# RWatch.net
KiCad netlist of a schematic drawn in EAGLE
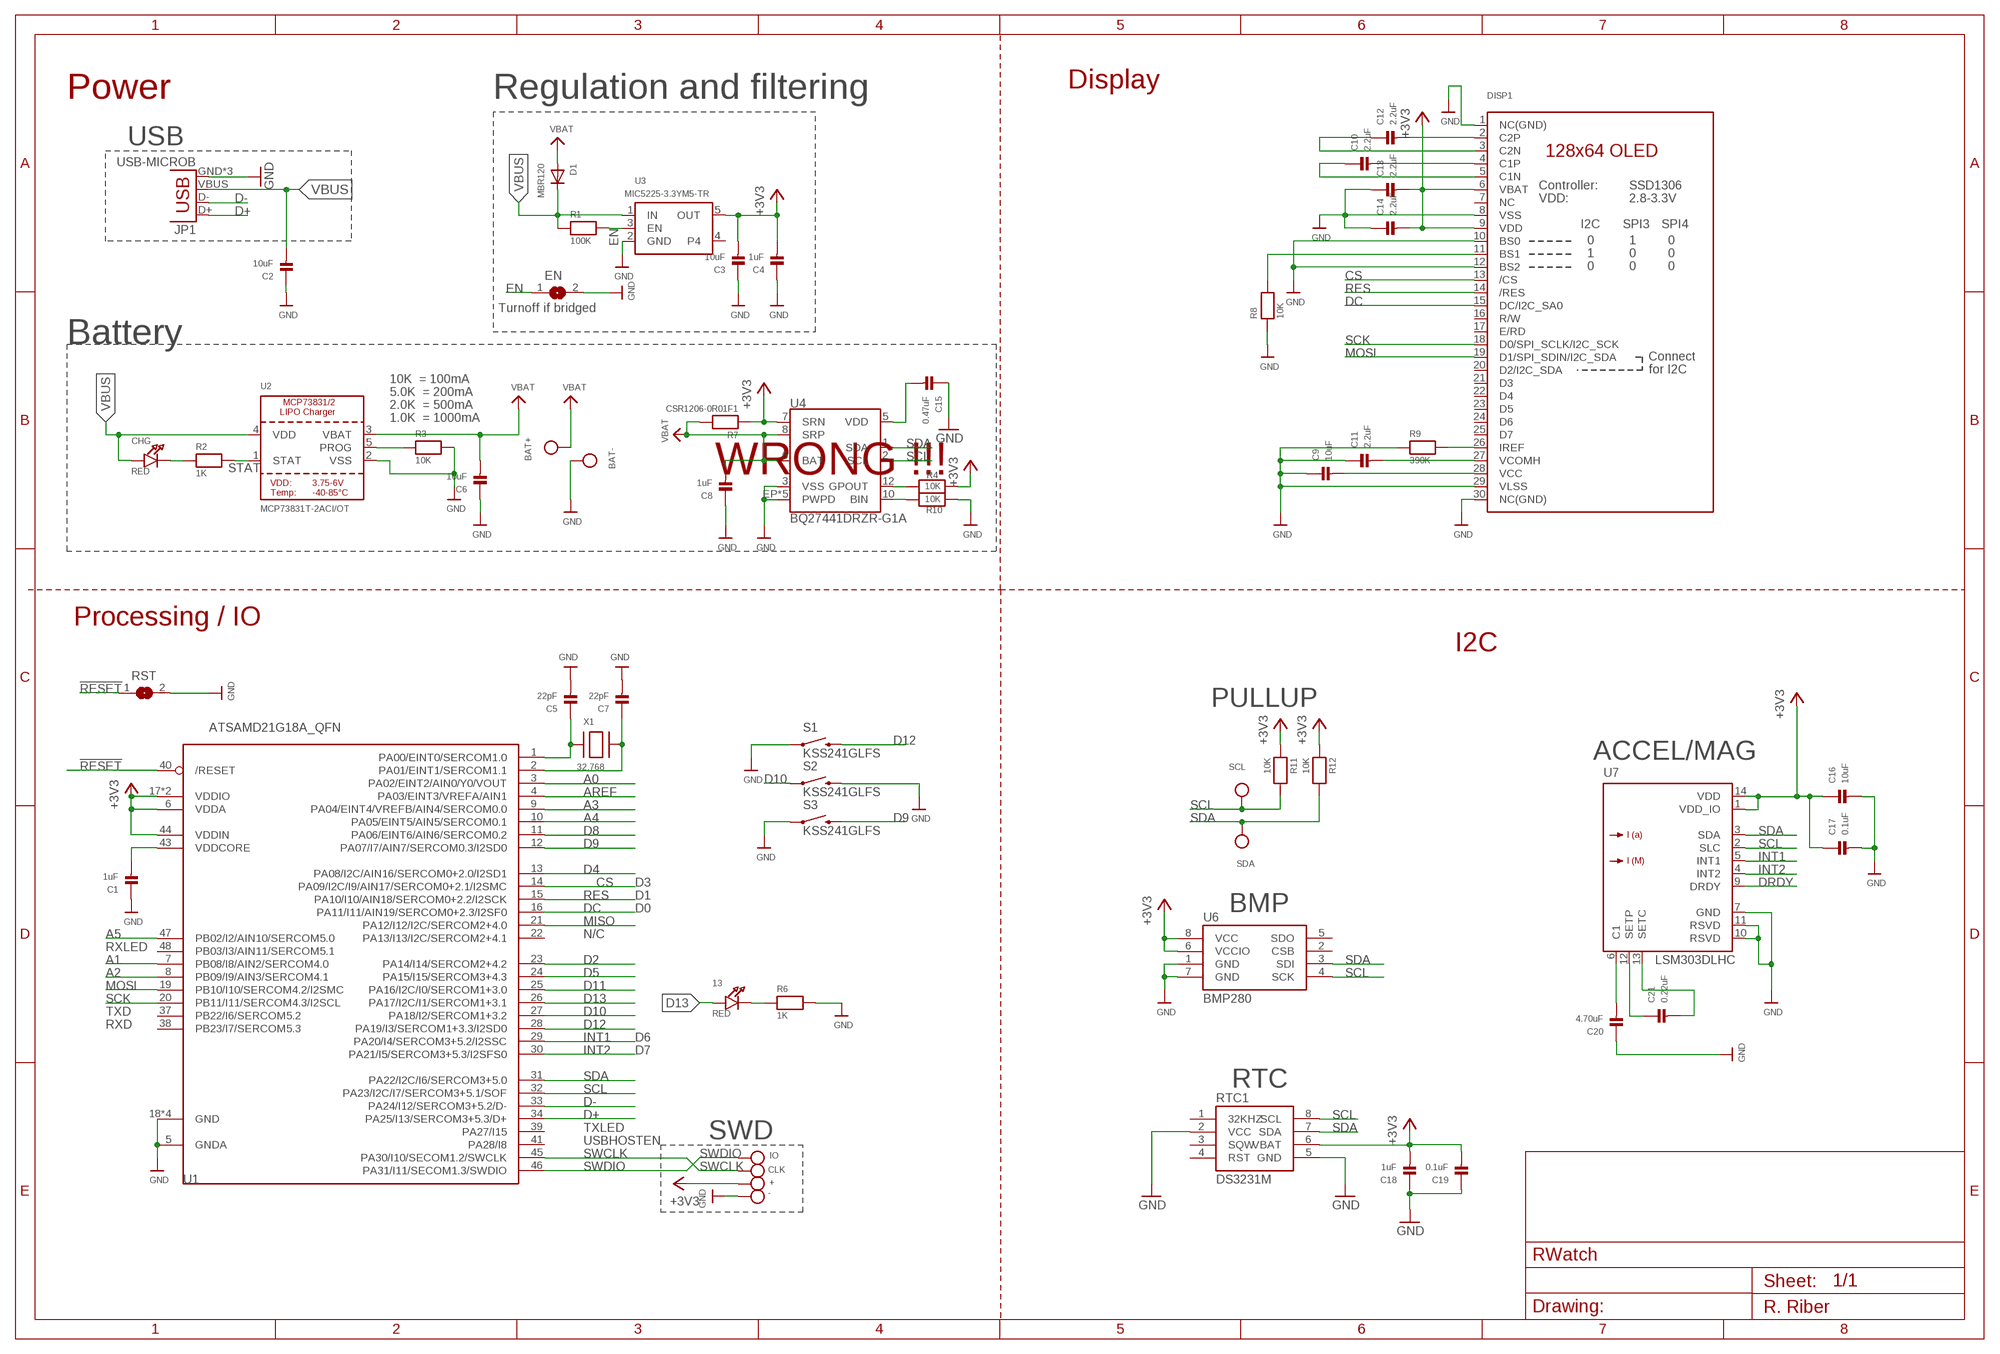
[diagram p0: schematic, sheet 1]

(export (version "E")
  (design (tool "Eeschema 10.0.6"))
  (components
    (comp (ref "+")
      (value "TESTPOINTROUND1MM")
      (footprint "eagle-import:TESTPOINT_ROUND_1MM")
      (libsource (lib "eagle-import") (part "TESTPOINTROUND1MM"))
    )
    (comp (ref "-")
      (value "TESTPOINTROUND1MM")
      (footprint "eagle-import:TESTPOINT_ROUND_1MM")
      (libsource (lib "eagle-import") (part "TESTPOINTROUND1MM"))
    )
    (comp (ref "13")
      (value "RED")
      (footprint "eagle-import:CHIPLED_0805")
      (fields (field (name "MF") "OSRAM") (field (name "MPN") "LGQ971"))
      (libsource (lib "eagle-import") (part "LED0805"))
    )
    (comp (ref "BAT+")
      (value "TESTPOINTROUND2MM")
      (footprint "eagle-import:TESTPOINT_ROUND_2MM")
      (libsource (lib "eagle-import") (part "TESTPOINTROUND2MM"))
    )
    (comp (ref "BAT-")
      (value "TESTPOINTROUND2MM")
      (footprint "eagle-import:TESTPOINT_ROUND_2MM")
      (libsource (lib "eagle-import") (part "TESTPOINTROUND2MM"))
    )
    (comp (ref "C1")
      (value "1uF")
      (footprint "eagle-import:0402")
      (libsource (lib "eagle-import") (part "CAP_CERAMIC0402"))
    )
    (comp (ref "C2")
      (value "10uF")
      (footprint "eagle-import:0603")
      (libsource (lib "eagle-import") (part "CAP_CERAMIC0603"))
    )
    (comp (ref "C3")
      (value "10uF")
      (footprint "eagle-import:0603")
      (libsource (lib "eagle-import") (part "CAP_CERAMIC0603"))
    )
    (comp (ref "C4")
      (value "1uF")
      (footprint "eagle-import:0402")
      (libsource (lib "eagle-import") (part "CAP_CERAMIC0402"))
    )
    (comp (ref "C5")
      (value "22pF")
      (footprint "eagle-import:0402")
      (libsource (lib "eagle-import") (part "CAP_CERAMIC0402"))
    )
    (comp (ref "C6")
      (value "10uF")
      (footprint "eagle-import:0603")
      (libsource (lib "eagle-import") (part "CAP_CERAMIC0603"))
    )
    (comp (ref "C7")
      (value "22pF")
      (footprint "eagle-import:0402")
      (libsource (lib "eagle-import") (part "CAP_CERAMIC0402"))
    )
    (comp (ref "C8")
      (value "1uF")
      (footprint "eagle-import:0402")
      (libsource (lib "eagle-import") (part "CAP_CERAMIC0402"))
    )
    (comp (ref "C9")
      (value "10uF")
      (footprint "eagle-import:0603")
      (libsource (lib "eagle-import") (part "CAP_CERAMIC0603"))
    )
    (comp (ref "C10")
      (value "2.2uF")
      (footprint "eagle-import:0402")
      (libsource (lib "eagle-import") (part "CAP_CERAMIC0402"))
    )
    (comp (ref "C11")
      (value "2.2uF")
      (footprint "eagle-import:0402")
      (libsource (lib "eagle-import") (part "CAP_CERAMIC0402"))
    )
    (comp (ref "C12")
      (value "2.2uF")
      (footprint "eagle-import:0402")
      (libsource (lib "eagle-import") (part "CAP_CERAMIC0402"))
    )
    (comp (ref "C13")
      (value "2.2uF")
      (footprint "eagle-import:0402")
      (libsource (lib "eagle-import") (part "CAP_CERAMIC0402"))
    )
    (comp (ref "C14")
      (value "2.2uF")
      (footprint "eagle-import:0402")
      (libsource (lib "eagle-import") (part "CAP_CERAMIC0402"))
    )
    (comp (ref "C15")
      (value "0.47uF")
      (footprint "eagle-import:0402")
      (libsource (lib "eagle-import") (part "CAP_CERAMIC0402"))
    )
    (comp (ref "C16")
      (value "10uF")
      (footprint "eagle-import:0603")
      (libsource (lib "eagle-import") (part "CAP_CERAMIC0603"))
    )
    (comp (ref "C17")
      (value "0.1uF")
      (footprint "eagle-import:0402")
      (libsource (lib "eagle-import") (part "CAP_CERAMIC0402"))
    )
    (comp (ref "C18")
      (value "1uF")
      (footprint "eagle-import:0402")
      (libsource (lib "eagle-import") (part "CAP_CERAMIC0402"))
    )
    (comp (ref "C19")
      (value "0.1uF")
      (footprint "eagle-import:0402")
      (libsource (lib "eagle-import") (part "CAP_CERAMIC0402"))
    )
    (comp (ref "C20")
      (value "4.70uF")
      (footprint "eagle-import:0402")
      (libsource (lib "eagle-import") (part "CAP_CERAMIC0402"))
    )
    (comp (ref "C21")
      (value "0.22uF")
      (footprint "eagle-import:0402")
      (libsource (lib "eagle-import") (part "CAP_CERAMIC0402"))
    )
    (comp (ref "CHG")
      (value "RED")
      (footprint "eagle-import:CHIPLED_0805")
      (fields (field (name "MF") "OSRAM") (field (name "MPN") "LGQ971"))
      (libsource (lib "eagle-import") (part "LED0805"))
    )
    (comp (ref "CLK")
      (value "TESTPOINTROUND1MM")
      (footprint "eagle-import:TESTPOINT_ROUND_1MM")
      (libsource (lib "eagle-import") (part "TESTPOINTROUND1MM"))
    )
    (comp (ref "D1")
      (value "MBR120")
      (footprint "eagle-import:SOD-123")
      (fields (field (name "MF") "ON SEMICONDUCTOR") (field (name "MPN") "MBR120VLSFT1G"))
      (libsource (lib "eagle-import") (part "DIODESOD-123"))
    )
    (comp (ref "DISP1")
      (value "DISP_OLED_UG-2864HSWEG01")
      (footprint "eagle-import:UG-2864HSWEG01_1.3_WRAPAROUND")
      (libsource (lib "eagle-import") (part "DISP_OLED_UG-2864HSWEG01"))
    )
    (comp (ref "EN")
      (value "SOLDERJUMPERREFLOW_NOPASTE")
      (footprint "eagle-import:SOLDERJUMPER_REFLOW_NOPASTE")
      (libsource (lib "eagle-import") (part "SOLDERJUMPERREFLOW_NOPASTE"))
    )
    (comp (ref "IO")
      (value "TESTPOINTROUND1MM")
      (footprint "eagle-import:TESTPOINT_ROUND_1MM")
      (libsource (lib "eagle-import") (part "TESTPOINTROUND1MM"))
    )
    (comp (ref "JP1")
      (value "USB-MICROB")
      (footprint "eagle-import:USB-MICROB")
      (fields (field (name "MF") "FCI") (field (name "MPN") "10104110-0001LF"))
      (libsource (lib "eagle-import") (part "USB-MICROB"))
    )
    (comp (ref "R1")
      (value "100K")
      (footprint "eagle-import:0402")
      (fields (field (name "MF") "MULTICOMP") (field (name "MPN") "MC0063W06031221R"))
      (libsource (lib "eagle-import") (part "RESISTOR0402"))
    )
    (comp (ref "R2")
      (value "1K")
      (footprint "eagle-import:0402")
      (fields (field (name "MF") "MULTICOMP") (field (name "MPN") "MC0063W06031221R"))
      (libsource (lib "eagle-import") (part "RESISTOR0402"))
    )
    (comp (ref "R3")
      (value "10K")
      (footprint "eagle-import:0402")
      (fields (field (name "MF") "VISHAY") (field (name "MPN") "CRCW060310K0JNEA"))
      (libsource (lib "eagle-import") (part "RESISTOR0402"))
    )
    (comp (ref "R4")
      (value "10K")
      (footprint "eagle-import:0402")
      (fields (field (name "MF") "VISHAY") (field (name "MPN") "CRCW060310K0FKEA"))
      (libsource (lib "eagle-import") (part "RESISTOR0402"))
    )
    (comp (ref "R6")
      (value "1K")
      (footprint "eagle-import:0402")
      (fields (field (name "MF") "VISHAY") (field (name "MPN") "CRCW06032K20JNEA"))
      (libsource (lib "eagle-import") (part "RESISTOR0402"))
    )
    (comp (ref "R7")
      (value "CSR1206-0R01F1")
      (footprint "eagle-import:1206")
      (libsource (lib "eagle-import") (part "RESISTOR1206"))
    )
    (comp (ref "R8")
      (value "10K")
      (footprint "eagle-import:0402")
      (libsource (lib "eagle-import") (part "RESISTOR0402"))
    )
    (comp (ref "R9")
      (value "390K")
      (footprint "eagle-import:0402")
      (libsource (lib "eagle-import") (part "RESISTOR0402"))
    )
    (comp (ref "R10")
      (value "10K")
      (footprint "eagle-import:0402")
      (fields (field (name "MF") "VISHAY") (field (name "MPN") "CRCW060310K0FKEA"))
      (libsource (lib "eagle-import") (part "RESISTOR0402"))
    )
    (comp (ref "R11")
      (value "10K")
      (footprint "eagle-import:0402")
      (fields (field (name "MF") "VISHAY") (field (name "MPN") "CRCW060310K0FKEA"))
      (libsource (lib "eagle-import") (part "RESISTOR0402"))
    )
    (comp (ref "R12")
      (value "10K")
      (footprint "eagle-import:0402")
      (fields (field (name "MF") "VISHAY") (field (name "MPN") "CRCW060310K0FKEA"))
      (libsource (lib "eagle-import") (part "RESISTOR0402"))
    )
    (comp (ref "RST")
      (value "SOLDERJUMPERREFLOW_NOPASTE")
      (footprint "eagle-import:SOLDERJUMPER_REFLOW_NOPASTE")
      (libsource (lib "eagle-import") (part "SOLDERJUMPERREFLOW_NOPASTE"))
    )
    (comp (ref "RTC1")
      (value "DS3231M")
      (footprint "eagle-import:SOIC8")
      (fields (field (name "MF") "MAXIM INTEGRATED PRODUCTS") (field (name "MPN") "DS3231MZ+TRL"))
      (libsource (lib "eagle-import") (part "DS3231M"))
    )
    (comp (ref "S1")
      (value "KSS241GLFS")
      (footprint "eagle-import:KSS241GLFS")
      (libsource (lib "eagle-import") (part "KSS241GLFS"))
    )
    (comp (ref "S2")
      (value "KSS241GLFS")
      (footprint "eagle-import:KSS241GLFS")
      (libsource (lib "eagle-import") (part "KSS241GLFS"))
    )
    (comp (ref "S3")
      (value "KSS241GLFS")
      (footprint "eagle-import:KSS241GLFS")
      (libsource (lib "eagle-import") (part "KSS241GLFS"))
    )
    (comp (ref "SCL")
      (value "TESTPOINTROUND1MM")
      (footprint "eagle-import:TESTPOINT_ROUND_1MM")
      (libsource (lib "eagle-import") (part "TESTPOINTROUND1MM"))
    )
    (comp (ref "SDA")
      (value "TESTPOINTROUND1MM")
      (footprint "eagle-import:TESTPOINT_ROUND_1MM")
      (libsource (lib "eagle-import") (part "TESTPOINTROUND1MM"))
    )
    (comp (ref "U1")
      (value "ATSAMD21G18A_QFN")
      (footprint "eagle-import:TQFN48_7MM")
      (libsource (lib "eagle-import") (part "ATSAMD21G18A_QFN"))
    )
    (comp (ref "U2")
      (value "MCP73831T-2ACI/OT")
      (footprint "eagle-import:SOT23-5@1")
      (fields (field (name "MF") "MICROCHIP"))
      (libsource (lib "eagle-import") (part "MCP73831/2"))
    )
    (comp (ref "U3")
      (value "MIC5225-3.3YM5-TR")
      (footprint "eagle-import:SOT23-5")
      (fields (field (name "MF") "MICROCHIP"))
      (libsource (lib "eagle-import") (part "VREG_SOT23-5"))
    )
    (comp (ref "U4")
      (value "BQ27441DRZR-G1A")
      (footprint "eagle-import:PDSO-N12")
      (libsource (lib "eagle-import") (part "BQ27441-G1"))
    )
    (comp (ref "U6")
      (value "BMP280")
      (footprint "eagle-import:LGA8")
      (libsource (lib "eagle-import") (part "BMP280"))
    )
    (comp (ref "U7")
      (value "LSM303DLHC")
      (footprint "eagle-import:LGA-14")
      (libsource (lib "eagle-import") (part "LSM303DLHC"))
    )
    (comp (ref "X1")
      (value "32.768")
      (footprint "eagle-import:XTAL3215")
      (libsource (lib "eagle-import") (part "XTAL-3.2X1.5"))
    )
  )
  (nets
    (net (code "1") (name "+3V3") (class "Default")
      (node (ref "+") (pin "P$1") (pinfunction "P$1_P$1") (pintype "bidirectional"))
      (node (ref "C13") (pin "2") (pinfunction "P$2_2") (pintype "passive"))
      (node (ref "C14") (pin "2") (pinfunction "P$2_2") (pintype "passive"))
      (node (ref "C16") (pin "1") (pinfunction "P$1_1") (pintype "passive"))
      (node (ref "C17") (pin "1") (pinfunction "P$1_1") (pintype "passive"))
      (node (ref "C18") (pin "2") (pinfunction "P$2_2") (pintype "passive"))
      (node (ref "C19") (pin "2") (pinfunction "P$2_2") (pintype "passive"))
      (node (ref "C3") (pin "2") (pinfunction "P$2_2") (pintype "passive"))
      (node (ref "C4") (pin "2") (pinfunction "P$2_2") (pintype "passive"))
      (node (ref "DISP1") (pin "6") (pinfunction "VBAT_6") (pintype "input"))
      (node (ref "DISP1") (pin "9") (pinfunction "VDD_9") (pintype "power_in"))
      (node (ref "R11") (pin "1") (pinfunction "1_1") (pintype "passive"))
      (node (ref "R12") (pin "1") (pinfunction "1_1") (pintype "passive"))
      (node (ref "R4") (pin "1") (pinfunction "1_1") (pintype "passive"))
      (node (ref "R7") (pin "1") (pinfunction "1_1") (pintype "passive"))
      (node (ref "RTC1") (pin "6") (pinfunction "VBAT_6") (pintype "power_in"))
      (node (ref "U1") (pin "17") (pinfunction "VDDIO_17") (pintype "power_in"))
      (node (ref "U1") (pin "36") (pinfunction "VDDIO_36") (pintype "power_in"))
      (node (ref "U1") (pin "44") (pinfunction "VDDIN_44") (pintype "power_in"))
      (node (ref "U1") (pin "6") (pinfunction "VDDA_6") (pintype "power_in"))
      (node (ref "U3") (pin "5") (pinfunction "OUT_5") (pintype "bidirectional"))
      (node (ref "U4") (pin "7") (pinfunction "SRN_7") (pintype "bidirectional"))
      (node (ref "U6") (pin "6") (pinfunction "VCCIO_6") (pintype "power_in"))
      (node (ref "U6") (pin "8") (pinfunction "VCC_8") (pintype "power_in"))
      (node (ref "U7") (pin "1") (pinfunction "VDD_IO_1") (pintype "power_in"))
      (node (ref "U7") (pin "14") (pinfunction "VDD_14") (pintype "power_in"))
    )
    (net (code "2") (name "/A0") (class "Default")
      (node (ref "U1") (pin "3") (pinfunction "PA02/EINT2/AIN0/Y0/VOUT_3") (pintype "bidirectional"))
    )
    (net (code "3") (name "/A1") (class "Default")
      (node (ref "U1") (pin "7") (pinfunction "PB08/I8/AIN2/SERCOM4.0_7") (pintype "bidirectional"))
    )
    (net (code "4") (name "/A2") (class "Default")
      (node (ref "U1") (pin "8") (pinfunction "PB09/I9/AIN3/SERCOM4.1_8") (pintype "bidirectional"))
    )
    (net (code "5") (name "/A3") (class "Default")
      (node (ref "U1") (pin "9") (pinfunction "PA04/EINT4/VREFB/AIN4/SERCOM0.0_9") (pintype "bidirectional"))
    )
    (net (code "6") (name "/A4") (class "Default")
      (node (ref "U1") (pin "10") (pinfunction "PA05/EINT5/AIN5/SERCOM0.1_10") (pintype "bidirectional"))
    )
    (net (code "7") (name "/A5") (class "Default")
      (node (ref "U1") (pin "47") (pinfunction "PB02/I2/AIN10/SERCOM5.0_47") (pintype "bidirectional"))
    )
    (net (code "8") (name "/AREF") (class "Default")
      (node (ref "U1") (pin "4") (pinfunction "PA03/EINT3/VREFA/AIN1_4") (pintype "bidirectional"))
    )
    (net (code "9") (name "/CS") (class "Default")
      (node (ref "DISP1") (pin "13") (pinfunction "/CS_13") (pintype "input"))
      (node (ref "U1") (pin "14") (pinfunction "PA09/I2C/I9/AIN17/SERCOM0+2.1/I2SMC_14") (pintype "bidirectional"))
    )
    (net (code "10") (name "/D+") (class "Default")
      (node (ref "JP1") (pin "D+") (pinfunction "D+_D+") (pintype "bidirectional"))
      (node (ref "U1") (pin "34") (pinfunction "PA25/I13/SERCOM3+5.3/D+_34") (pintype "bidirectional"))
    )
    (net (code "11") (name "/D-") (class "Default")
      (node (ref "JP1") (pin "D-") (pinfunction "D-_D-") (pintype "bidirectional"))
      (node (ref "U1") (pin "33") (pinfunction "PA24/I12/SERCOM3+5.2/D-_33") (pintype "bidirectional"))
    )
    (net (code "12") (name "/D2") (class "Default")
      (node (ref "U1") (pin "23") (pinfunction "PA14/I14/SERCOM2+4.2_23") (pintype "bidirectional"))
    )
    (net (code "13") (name "/D4") (class "Default")
      (node (ref "U1") (pin "13") (pinfunction "PA08/I2C/AIN16/SERCOM0+2.0/I2SD1_13") (pintype "bidirectional"))
    )
    (net (code "14") (name "/D5") (class "Default")
      (node (ref "U1") (pin "24") (pinfunction "PA15/I15/SERCOM3+4.3_24") (pintype "bidirectional"))
    )
    (net (code "15") (name "/D8") (class "Default")
      (node (ref "U1") (pin "11") (pinfunction "PA06/EINT6/AIN6/SERCOM0.2_11") (pintype "bidirectional"))
    )
    (net (code "16") (name "/D9") (class "Default")
      (node (ref "S3") (pin "2") (pinfunction "2_2") (pintype "passive"))
      (node (ref "U1") (pin "12") (pinfunction "PA07/I7/AIN7/SERCOM0.3/I2SD0_12") (pintype "bidirectional"))
    )
    (net (code "17") (name "/D10") (class "Default")
      (node (ref "S2") (pin "1") (pinfunction "1_1") (pintype "passive"))
      (node (ref "U1") (pin "27") (pinfunction "PA18/I2/SERCOM1+3.2_27") (pintype "bidirectional"))
    )
    (net (code "18") (name "/D11") (class "Default")
      (node (ref "U1") (pin "25") (pinfunction "PA16/I2C/I0/SERCOM1+3.0_25") (pintype "bidirectional"))
    )
    (net (code "19") (name "/D12") (class "Default")
      (node (ref "S1") (pin "2") (pinfunction "2_2") (pintype "passive"))
      (node (ref "U1") (pin "28") (pinfunction "PA19/I3/SERCOM1+3.3/I2SD0_28") (pintype "bidirectional"))
    )
    (net (code "20") (name "/DC") (class "Default")
      (node (ref "DISP1") (pin "15") (pinfunction "DC/I2C_SA0_15") (pintype "input"))
      (node (ref "U1") (pin "16") (pinfunction "PA11/I11/AIN19/SERCOM0+2.3/I2SF0_16") (pintype "bidirectional"))
    )
    (net (code "21") (name "/DRDY") (class "Default")
      (node (ref "U7") (pin "9") (pinfunction "DRDY_9") (pintype "bidirectional"))
    )
    (net (code "22") (name "/EN") (class "Default")
      (node (ref "EN") (pin "1") (pinfunction "1_1") (pintype "passive"))
      (node (ref "R1") (pin "2") (pinfunction "2_2") (pintype "passive"))
      (node (ref "U3") (pin "3") (pinfunction "EN_3") (pintype "bidirectional"))
    )
    (net (code "23") (name "/INT1") (class "Default")
      (node (ref "U1") (pin "29") (pinfunction "PA20/I4/SERCOM3+5.2/I2SSC_29") (pintype "bidirectional"))
      (node (ref "U7") (pin "5") (pinfunction "INT1_5") (pintype "bidirectional"))
    )
    (net (code "24") (name "/INT2") (class "Default")
      (node (ref "U1") (pin "30") (pinfunction "PA21/I5/SERCOM3+5.3/I2SFS0_30") (pintype "bidirectional"))
      (node (ref "U7") (pin "4") (pinfunction "INT2_4") (pintype "bidirectional"))
    )
    (net (code "25") (name "/MISO") (class "Default")
      (node (ref "U1") (pin "21") (pinfunction "PA12/I12/I2C/SERCOM2+4.0_21") (pintype "bidirectional"))
    )
    (net (code "26") (name "/MOSI") (class "Default")
      (node (ref "DISP1") (pin "19") (pinfunction "D1/SPI_SDIN/I2C_SDA_19") (pintype "bidirectional"))
      (node (ref "U1") (pin "19") (pinfunction "PB10/I10/SERCOM4.2/I2SMC_19") (pintype "bidirectional"))
    )
    (net (code "27") (name "/RES") (class "Default")
      (node (ref "DISP1") (pin "14") (pinfunction "/RES_14") (pintype "input"))
      (node (ref "U1") (pin "15") (pinfunction "PA10/I10/AIN18/SERCOM0+2.2/I2SCK_15") (pintype "bidirectional"))
    )
    (net (code "28") (name "/SCK") (class "Default")
      (node (ref "DISP1") (pin "18") (pinfunction "D0/SPI_SCLK/I2C_SCK_18") (pintype "bidirectional"))
      (node (ref "U1") (pin "20") (pinfunction "PB11/I11/SERCOM4.3/I2SCL_20") (pintype "bidirectional"))
    )
    (net (code "29") (name "/SCL") (class "Default")
      (node (ref "R11") (pin "2") (pinfunction "2_2") (pintype "passive"))
      (node (ref "RTC1") (pin "8") (pinfunction "SCL_8") (pintype "bidirectional"))
      (node (ref "SCL") (pin "P$1") (pinfunction "P$1_P$1") (pintype "bidirectional"))
      (node (ref "U1") (pin "32") (pinfunction "PA23/I2C/I7/SERCOM3+5.1/SOF_32") (pintype "bidirectional"))
      (node (ref "U4") (pin "2") (pinfunction "SCL_2") (pintype "bidirectional"))
      (node (ref "U6") (pin "4") (pinfunction "SCK_4") (pintype "bidirectional"))
      (node (ref "U7") (pin "2") (pinfunction "SLC_2") (pintype "bidirectional"))
    )
    (net (code "30") (name "/SDA") (class "Default")
      (node (ref "R12") (pin "2") (pinfunction "2_2") (pintype "passive"))
      (node (ref "RTC1") (pin "7") (pinfunction "SDA_7") (pintype "bidirectional"))
      (node (ref "SDA") (pin "P$1") (pinfunction "P$1_P$1") (pintype "bidirectional"))
      (node (ref "U1") (pin "31") (pinfunction "PA22/I2C/I6/SERCOM3+5.0_31") (pintype "bidirectional"))
      (node (ref "U4") (pin "1") (pinfunction "SDA_1") (pintype "bidirectional"))
      (node (ref "U6") (pin "3") (pinfunction "SDI_3") (pintype "bidirectional"))
      (node (ref "U7") (pin "3") (pinfunction "SDA_3") (pintype "bidirectional"))
    )
    (net (code "31") (name "/STAT") (class "Default")
      (node (ref "R2") (pin "2") (pinfunction "2_2") (pintype "passive"))
      (node (ref "U2") (pin "1") (pinfunction "STAT_1") (pintype "output"))
    )
    (net (code "32") (name "/SWCLK") (class "Default")
      (node (ref "CLK") (pin "P$1") (pinfunction "P$1_P$1") (pintype "bidirectional"))
      (node (ref "U1") (pin "45") (pinfunction "PA30/I10/SECOM1.2/SWCLK_45") (pintype "bidirectional"))
    )
    (net (code "33") (name "/SWDIO") (class "Default")
      (node (ref "IO") (pin "P$1") (pinfunction "P$1_P$1") (pintype "bidirectional"))
      (node (ref "U1") (pin "46") (pinfunction "PA31/I11/SECOM1.3/SWDIO_46") (pintype "bidirectional"))
    )
    (net (code "34") (name "/~{RESET}") (class "Default")
      (node (ref "RST") (pin "1") (pinfunction "1_1") (pintype "passive"))
      (node (ref "U1") (pin "40") (pinfunction "/RESET_40") (pintype "bidirectional"))
    )
    (net (code "35") (name "D13") (class "Default")
      (node (ref "13") (pin "A") (pinfunction "A_A") (pintype "passive"))
      (node (ref "U1") (pin "26") (pinfunction "PA17/I2C/I1/SERCOM1+3.1_26") (pintype "bidirectional"))
    )
    (net (code "36") (name "GND") (class "Default")
      (node (ref "-") (pin "P$1") (pinfunction "P$1_P$1") (pintype "bidirectional"))
      (node (ref "BAT-") (pin "P$1") (pinfunction "P$1_P$1") (pintype "bidirectional"))
      (node (ref "C1") (pin "1") (pinfunction "P$1_1") (pintype "passive"))
      (node (ref "C11") (pin "1") (pinfunction "P$1_1") (pintype "passive"))
      (node (ref "C13") (pin "1") (pinfunction "P$1_1") (pintype "passive"))
      (node (ref "C14") (pin "1") (pinfunction "P$1_1") (pintype "passive"))
      (node (ref "C15") (pin "1") (pinfunction "P$1_1") (pintype "passive"))
      (node (ref "C16") (pin "2") (pinfunction "P$2_2") (pintype "passive"))
      (node (ref "C17") (pin "2") (pinfunction "P$2_2") (pintype "passive"))
      (node (ref "C18") (pin "1") (pinfunction "P$1_1") (pintype "passive"))
      (node (ref "C19") (pin "1") (pinfunction "P$1_1") (pintype "passive"))
      (node (ref "C2") (pin "1") (pinfunction "P$1_1") (pintype "passive"))
      (node (ref "C20") (pin "1") (pinfunction "P$1_1") (pintype "passive"))
      (node (ref "C3") (pin "1") (pinfunction "P$1_1") (pintype "passive"))
      (node (ref "C4") (pin "1") (pinfunction "P$1_1") (pintype "passive"))
      (node (ref "C5") (pin "2") (pinfunction "P$2_2") (pintype "passive"))
      (node (ref "C6") (pin "1") (pinfunction "P$1_1") (pintype "passive"))
      (node (ref "C7") (pin "2") (pinfunction "P$2_2") (pintype "passive"))
      (node (ref "C8") (pin "1") (pinfunction "P$1_1") (pintype "passive"))
      (node (ref "C9") (pin "1") (pinfunction "P$1_1") (pintype "passive"))
      (node (ref "DISP1") (pin "1") (pinfunction "NC(GND)_1") (pintype "input"))
      (node (ref "DISP1") (pin "10") (pinfunction "BS0_10") (pintype "input"))
      (node (ref "DISP1") (pin "12") (pinfunction "BS2_12") (pintype "input"))
      (node (ref "DISP1") (pin "29") (pinfunction "VLSS_29") (pintype "power_in"))
      (node (ref "DISP1") (pin "30") (pinfunction "NC(GND)_30") (pintype "input"))
      (node (ref "DISP1") (pin "8") (pinfunction "VSS_8") (pintype "power_in"))
      (node (ref "EN") (pin "2") (pinfunction "2_2") (pintype "passive"))
      (node (ref "JP1") (pin "GND") (pinfunction "GND_GND") (pintype "bidirectional"))
      (node (ref "JP1") (pin "MT1") (pinfunction "GND_MT1") (pintype "bidirectional"))
      (node (ref "JP1") (pin "MT2") (pinfunction "GND_MT2") (pintype "bidirectional"))
      (node (ref "R10") (pin "1") (pinfunction "1_1") (pintype "passive"))
      (node (ref "R3") (pin "2") (pinfunction "2_2") (pintype "passive"))
      (node (ref "R6") (pin "2") (pinfunction "2_2") (pintype "passive"))
      (node (ref "R8") (pin "1") (pinfunction "1_1") (pintype "passive"))
      (node (ref "R9") (pin "1") (pinfunction "1_1") (pintype "passive"))
      (node (ref "RST") (pin "2") (pinfunction "2_2") (pintype "passive"))
      (node (ref "RTC1") (pin "2") (pinfunction "VCC_2") (pintype "power_in"))
      (node (ref "RTC1") (pin "5") (pinfunction "GND_5") (pintype "power_in"))
      (node (ref "S1") (pin "1") (pinfunction "1_1") (pintype "passive"))
      (node (ref "S2") (pin "2") (pinfunction "2_2") (pintype "passive"))
      (node (ref "S3") (pin "1") (pinfunction "1_1") (pintype "passive"))
      (node (ref "U1") (pin "18") (pinfunction "GND_18") (pintype "power_in"))
      (node (ref "U1") (pin "35") (pinfunction "GND_35") (pintype "power_in"))
      (node (ref "U1") (pin "42") (pinfunction "GND_42") (pintype "power_in"))
      (node (ref "U1") (pin "5") (pinfunction "GNDA_5") (pintype "power_in"))
      (node (ref "U1") (pin "THERMAL") (pinfunction "GND_THERMAL") (pintype "power_in"))
      (node (ref "U2") (pin "2") (pinfunction "VSS_2") (pintype "power_in"))
      (node (ref "U3") (pin "2") (pinfunction "GND_2") (pintype "bidirectional"))
      (node (ref "U4") (pin "3") (pinfunction "VSS_3") (pintype "bidirectional"))
      (node (ref "U4") (pin "EP") (pinfunction "PWPD_EP") (pintype "bidirectional"))
      (node (ref "U4") (pin "EP1") (pinfunction "PWPD_EP1") (pintype "bidirectional"))
      (node (ref "U4") (pin "EP2") (pinfunction "PWPD_EP2") (pintype "bidirectional"))
      (node (ref "U4") (pin "EP3") (pinfunction "PWPD_EP3") (pintype "bidirectional"))
      (node (ref "U4") (pin "EP4") (pinfunction "PWPD_EP4") (pintype "bidirectional"))
      (node (ref "U6") (pin "1") (pinfunction "GND_1") (pintype "power_in"))
      (node (ref "U6") (pin "7") (pinfunction "GND_7") (pintype "power_in"))
      (node (ref "U7") (pin "10") (pinfunction "RSVD_10") (pintype "passive"))
      (node (ref "U7") (pin "11") (pinfunction "RSVD_11") (pintype "passive"))
      (node (ref "U7") (pin "7") (pinfunction "GND_7") (pintype "power_in"))
    )
    (net (code "37") (name "Net-(13-PadC)") (class "Default")
      (node (ref "13") (pin "C") (pinfunction "C_C") (pintype "passive"))
      (node (ref "R6") (pin "1") (pinfunction "1_1") (pintype "passive"))
    )
    (net (code "38") (name "Net-(C1-P$2)") (class "Default")
      (node (ref "C1") (pin "2") (pinfunction "P$2_2") (pintype "passive"))
      (node (ref "U1") (pin "43") (pinfunction "VDDCORE_43") (pintype "power_in"))
    )
    (net (code "39") (name "Net-(C5-P$1)") (class "Default")
      (node (ref "C5") (pin "1") (pinfunction "P$1_1") (pintype "passive"))
      (node (ref "U1") (pin "1") (pinfunction "PA00/EINT0/SERCOM1.0_1") (pintype "bidirectional"))
      (node (ref "X1") (pin "P$1") (pinfunction "P$1_P$1") (pintype "bidirectional"))
    )
    (net (code "40") (name "Net-(C7-P$1)") (class "Default")
      (node (ref "C7") (pin "1") (pinfunction "P$1_1") (pintype "passive"))
      (node (ref "U1") (pin "2") (pinfunction "PA01/EINT1/SERCOM1.1_2") (pintype "bidirectional"))
      (node (ref "X1") (pin "P$2") (pinfunction "P$2_P$2") (pintype "bidirectional"))
    )
    (net (code "41") (name "Net-(C9-P$2)") (class "Default")
      (node (ref "C9") (pin "2") (pinfunction "P$2_2") (pintype "passive"))
      (node (ref "DISP1") (pin "28") (pinfunction "VCC_28") (pintype "power_in"))
    )
    (net (code "42") (name "Net-(C10-P$1)") (class "Default")
      (node (ref "C10") (pin "1") (pinfunction "P$1_1") (pintype "passive"))
      (node (ref "DISP1") (pin "5") (pinfunction "C1N_5") (pintype "input"))
    )
    (net (code "43") (name "Net-(C10-P$2)") (class "Default")
      (node (ref "C10") (pin "2") (pinfunction "P$2_2") (pintype "passive"))
      (node (ref "DISP1") (pin "4") (pinfunction "C1P_4") (pintype "input"))
    )
    (net (code "44") (name "Net-(C11-P$2)") (class "Default")
      (node (ref "C11") (pin "2") (pinfunction "P$2_2") (pintype "passive"))
      (node (ref "DISP1") (pin "27") (pinfunction "VCOMH_27") (pintype "output"))
    )
    (net (code "45") (name "Net-(C12-P$1)") (class "Default")
      (node (ref "C12") (pin "1") (pinfunction "P$1_1") (pintype "passive"))
      (node (ref "DISP1") (pin "3") (pinfunction "C2N_3") (pintype "input"))
    )
    (net (code "46") (name "Net-(C12-P$2)") (class "Default")
      (node (ref "C12") (pin "2") (pinfunction "P$2_2") (pintype "passive"))
      (node (ref "DISP1") (pin "2") (pinfunction "C2P_2") (pintype "input"))
    )
    (net (code "47") (name "Net-(C15-P$2)") (class "Default")
      (node (ref "C15") (pin "2") (pinfunction "P$2_2") (pintype "passive"))
      (node (ref "U4") (pin "5") (pinfunction "VDD_5") (pintype "bidirectional"))
    )
    (net (code "48") (name "Net-(C20-P$2)") (class "Default")
      (node (ref "C20") (pin "2") (pinfunction "P$2_2") (pintype "passive"))
      (node (ref "U7") (pin "6") (pinfunction "C1_6") (pintype "passive"))
    )
    (net (code "49") (name "Net-(C21-P$1)") (class "Default")
      (node (ref "C21") (pin "1") (pinfunction "P$1_1") (pintype "passive"))
      (node (ref "U7") (pin "12") (pinfunction "SETP_12") (pintype "passive"))
    )
    (net (code "50") (name "Net-(C21-P$2)") (class "Default")
      (node (ref "C21") (pin "2") (pinfunction "P$2_2") (pintype "passive"))
      (node (ref "U7") (pin "13") (pinfunction "SETC_13") (pintype "passive"))
    )
    (net (code "51") (name "Net-(CHG-PadC)") (class "Default")
      (node (ref "CHG") (pin "C") (pinfunction "C_C") (pintype "passive"))
      (node (ref "R2") (pin "1") (pinfunction "1_1") (pintype "passive"))
    )
    (net (code "52") (name "Net-(DISP1-BS1)") (class "Default")
      (node (ref "DISP1") (pin "11") (pinfunction "BS1_11") (pintype "input"))
      (node (ref "R8") (pin "2") (pinfunction "2_2") (pintype "passive"))
    )
    (net (code "53") (name "Net-(DISP1-IREF)") (class "Default")
      (node (ref "DISP1") (pin "26") (pinfunction "IREF_26") (pintype "input"))
      (node (ref "R9") (pin "2") (pinfunction "2_2") (pintype "passive"))
    )
    (net (code "54") (name "Net-(U2-PROG)") (class "Default")
      (node (ref "R3") (pin "1") (pinfunction "1_1") (pintype "passive"))
      (node (ref "U2") (pin "5") (pinfunction "PROG_5") (pintype "input"))
    )
    (net (code "55") (name "Net-(U4-BIN)") (class "Default")
      (node (ref "R10") (pin "2") (pinfunction "2_2") (pintype "passive"))
      (node (ref "U4") (pin "10") (pinfunction "BIN_10") (pintype "bidirectional"))
    )
    (net (code "56") (name "Net-(U4-GPOUT)") (class "Default")
      (node (ref "R4") (pin "2") (pinfunction "2_2") (pintype "passive"))
      (node (ref "U4") (pin "12") (pinfunction "GPOUT_12") (pintype "bidirectional"))
    )
    (net (code "57") (name "VBAT") (class "Default")
      (node (ref "BAT+") (pin "P$1") (pinfunction "P$1_P$1") (pintype "bidirectional"))
      (node (ref "C6") (pin "2") (pinfunction "P$2_2") (pintype "passive"))
      (node (ref "C8") (pin "2") (pinfunction "P$2_2") (pintype "passive"))
      (node (ref "D1") (pin "A") (pinfunction "A_A") (pintype "passive"))
      (node (ref "R7") (pin "2") (pinfunction "2_2") (pintype "passive"))
      (node (ref "U2") (pin "3") (pinfunction "VBAT_3") (pintype "power_in"))
      (node (ref "U4") (pin "6") (pinfunction "BAT_6") (pintype "bidirectional"))
      (node (ref "U4") (pin "8") (pinfunction "SRP_8") (pintype "bidirectional"))
    )
    (net (code "58") (name "VBUS") (class "Default")
      (node (ref "C2") (pin "2") (pinfunction "P$2_2") (pintype "passive"))
      (node (ref "CHG") (pin "A") (pinfunction "A_A") (pintype "passive"))
      (node (ref "D1") (pin "C") (pinfunction "C_C") (pintype "passive"))
      (node (ref "JP1") (pin "VBUS") (pinfunction "VBUS_VBUS") (pintype "bidirectional"))
      (node (ref "R1") (pin "1") (pinfunction "1_1") (pintype "passive"))
      (node (ref "U2") (pin "4") (pinfunction "VDD_4") (pintype "power_in"))
      (node (ref "U3") (pin "1") (pinfunction "IN_1") (pintype "bidirectional"))
    )
    (net (code "59") (name "unconnected-(DISP1-D2{slash}I2C_SDA-Pad20)") (class "Default")
      (node (ref "DISP1") (pin "20") (pinfunction "D2/I2C_SDA_20") (pintype "bidirectional"))
    )
    (net (code "60") (name "unconnected-(DISP1-D3-Pad21)") (class "Default")
      (node (ref "DISP1") (pin "21") (pinfunction "D3_21") (pintype "bidirectional"))
    )
    (net (code "61") (name "unconnected-(DISP1-D4-Pad22)") (class "Default")
      (node (ref "DISP1") (pin "22") (pinfunction "D4_22") (pintype "bidirectional"))
    )
    (net (code "62") (name "unconnected-(DISP1-D5-Pad23)") (class "Default")
      (node (ref "DISP1") (pin "23") (pinfunction "D5_23") (pintype "bidirectional"))
    )
    (net (code "63") (name "unconnected-(DISP1-D6-Pad24)") (class "Default")
      (node (ref "DISP1") (pin "24") (pinfunction "D6_24") (pintype "bidirectional"))
    )
    (net (code "64") (name "unconnected-(DISP1-D7-Pad25)") (class "Default")
      (node (ref "DISP1") (pin "25") (pinfunction "D7_25") (pintype "bidirectional"))
    )
    (net (code "65") (name "unconnected-(DISP1-E{slash}RD-Pad17)") (class "Default")
      (node (ref "DISP1") (pin "17") (pinfunction "E/RD_17") (pintype "input"))
    )
    (net (code "66") (name "unconnected-(DISP1-NC-Pad7)") (class "Default")
      (node (ref "DISP1") (pin "7") (pinfunction "NC_7") (pintype "no_connect"))
    )
    (net (code "67") (name "unconnected-(DISP1-R{slash}W-Pad16)") (class "Default")
      (node (ref "DISP1") (pin "16") (pinfunction "R/W_16") (pintype "input"))
    )
    (net (code "68") (name "unconnected-(RTC1-32KHZ-Pad1)") (class "Default")
      (node (ref "RTC1") (pin "1") (pinfunction "32KHZ_1") (pintype "output"))
    )
    (net (code "69") (name "unconnected-(RTC1-RST-Pad4)") (class "Default")
      (node (ref "RTC1") (pin "4") (pinfunction "RST_4") (pintype "bidirectional"))
    )
    (net (code "70") (name "unconnected-(RTC1-SQW-Pad3)") (class "Default")
      (node (ref "RTC1") (pin "3") (pinfunction "SQW_3") (pintype "output"))
    )
    (net (code "71") (name "unconnected-(U1-PA13{slash}I13{slash}I2C{slash}SERCOM2+4.1-Pad22)") (class "Default")
      (node (ref "U1") (pin "22") (pinfunction "PA13/I13/I2C/SERCOM2+4.1_22") (pintype "bidirectional"))
    )
    (net (code "72") (name "unconnected-(U1-PA27{slash}I15-Pad39)") (class "Default")
      (node (ref "U1") (pin "39") (pinfunction "PA27/I15_39") (pintype "bidirectional"))
    )
    (net (code "73") (name "unconnected-(U1-PA28{slash}I8-Pad41)") (class "Default")
      (node (ref "U1") (pin "41") (pinfunction "PA28/I8_41") (pintype "bidirectional"))
    )
    (net (code "74") (name "unconnected-(U1-PB03{slash}I3{slash}AIN11{slash}SERCOM5.1-Pad48)") (class "Default")
      (node (ref "U1") (pin "48") (pinfunction "PB03/I3/AIN11/SERCOM5.1_48") (pintype "bidirectional"))
    )
    (net (code "75") (name "unconnected-(U1-PB22{slash}I6{slash}SERCOM5.2-Pad37)") (class "Default")
      (node (ref "U1") (pin "37") (pinfunction "PB22/I6/SERCOM5.2_37") (pintype "bidirectional"))
    )
    (net (code "76") (name "unconnected-(U1-PB23{slash}I7{slash}SERCOM5.3-Pad38)") (class "Default")
      (node (ref "U1") (pin "38") (pinfunction "PB23/I7/SERCOM5.3_38") (pintype "bidirectional"))
    )
    (net (code "77") (name "unconnected-(U3-P4-Pad4)") (class "Default")
      (node (ref "U3") (pin "4") (pinfunction "P4_4") (pintype "bidirectional"))
    )
    (net (code "78") (name "unconnected-(U6-CSB-Pad2)") (class "Default")
      (node (ref "U6") (pin "2") (pinfunction "CSB_2") (pintype "input"))
    )
    (net (code "79") (name "unconnected-(U6-SDO-Pad5)") (class "Default")
      (node (ref "U6") (pin "5") (pinfunction "SDO_5") (pintype "bidirectional"))
    )
  )
)
